# Digital_Port_K_State_LED_Inducator.net
KiCad netlist of a schematic drawn in Altium Designer
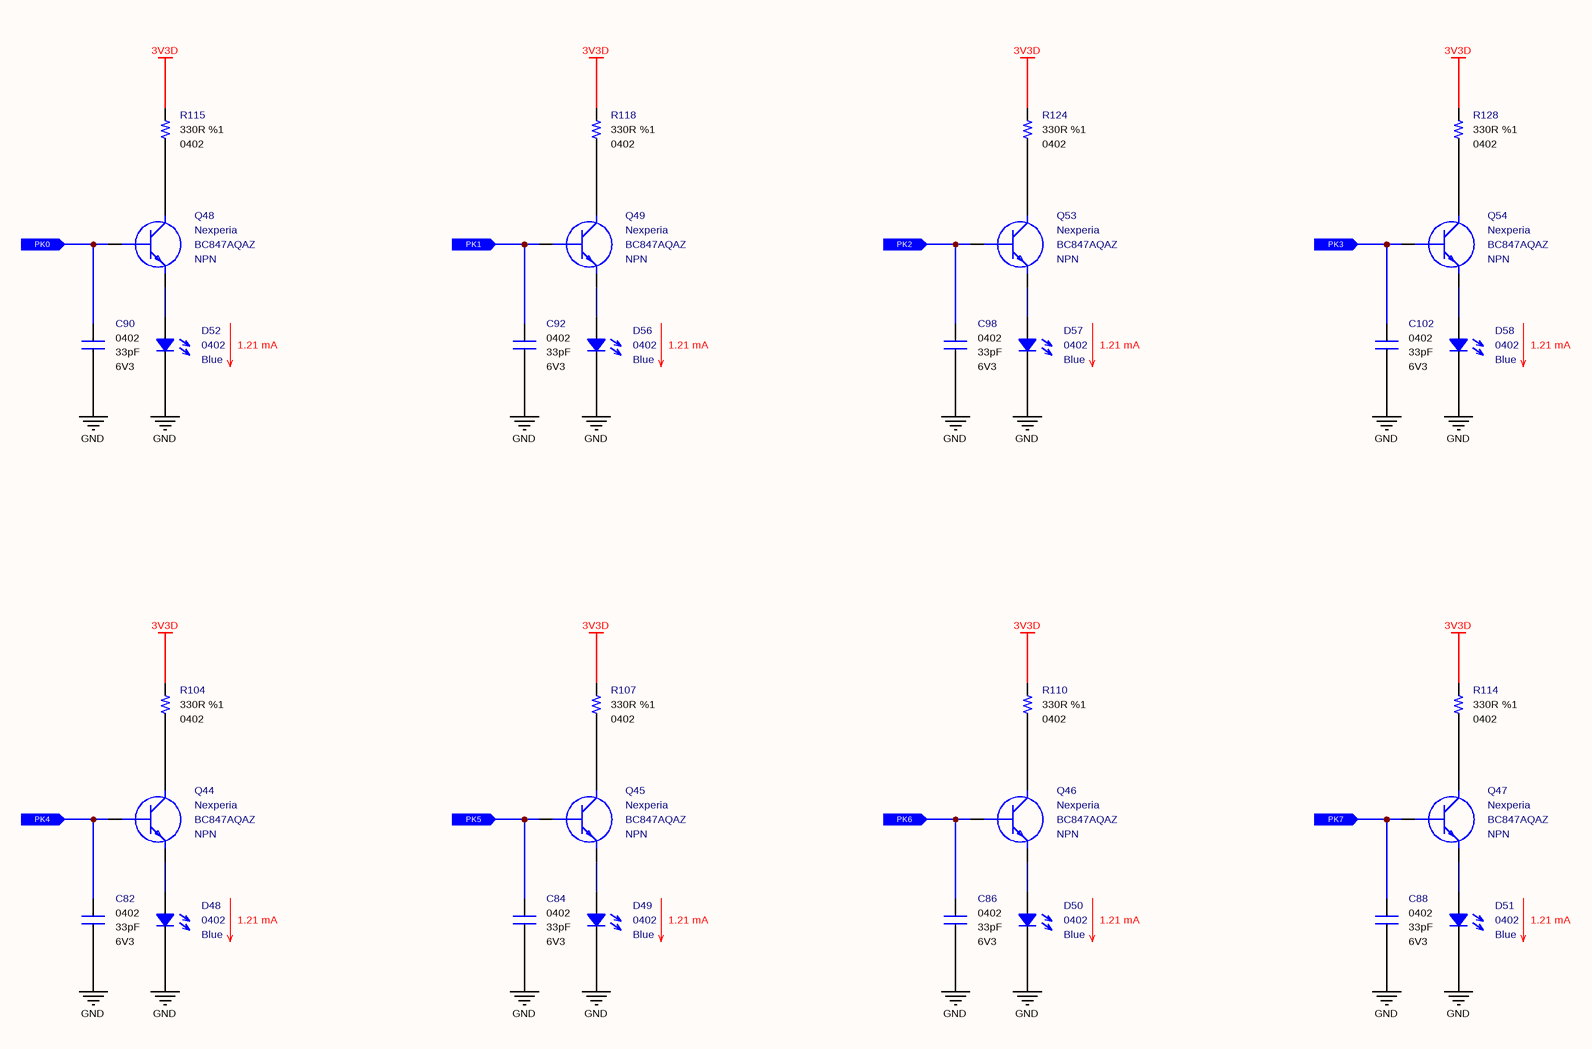
[diagram p0: Digital Port K State LED Inducator.SchDoc]

(export (version "E")
  (design (tool "Eeschema 10.0.6"))
  (components
    (comp (ref "C82")
      (value "33pF")
      (footprint "CAPACITOR_0402")
      (description "Capacitor - 33pF [0402] (Ceramic)")
      (fields
        (field (name "CASE") "0402")
        (field (name "TOLERANCE") "10%")
        (field (name "VOLTAGE") "6V3")
        (field (name "MANUFACTURER PART NUMBER") "C0402C330J9RACAUTO")
      )
      (libsource (lib "Ovoo_Library") (part "Capacitor - 33pF [0402-6V3]"))
    )
    (comp (ref "C84")
      (value "33pF")
      (footprint "CAPACITOR_0402")
      (description "Capacitor - 33pF [0402] (Ceramic)")
      (fields
        (field (name "CASE") "0402")
        (field (name "TOLERANCE") "10%")
        (field (name "VOLTAGE") "6V3")
        (field (name "MANUFACTURER PART NUMBER") "C0402C330J9RACAUTO")
      )
      (libsource (lib "Ovoo_Library") (part "Capacitor - 33pF [0402-6V3]"))
    )
    (comp (ref "C86")
      (value "33pF")
      (footprint "CAPACITOR_0402")
      (description "Capacitor - 33pF [0402] (Ceramic)")
      (fields
        (field (name "CASE") "0402")
        (field (name "TOLERANCE") "10%")
        (field (name "VOLTAGE") "6V3")
        (field (name "MANUFACTURER PART NUMBER") "C0402C330J9RACAUTO")
      )
      (libsource (lib "Ovoo_Library") (part "Capacitor - 33pF [0402-6V3]"))
    )
    (comp (ref "C88")
      (value "33pF")
      (footprint "CAPACITOR_0402")
      (description "Capacitor - 33pF [0402] (Ceramic)")
      (fields
        (field (name "CASE") "0402")
        (field (name "TOLERANCE") "10%")
        (field (name "VOLTAGE") "6V3")
        (field (name "MANUFACTURER PART NUMBER") "C0402C330J9RACAUTO")
      )
      (libsource (lib "Ovoo_Library") (part "Capacitor - 33pF [0402-6V3]"))
    )
    (comp (ref "C90")
      (value "33pF")
      (footprint "CAPACITOR_0402")
      (description "Capacitor - 33pF [0402] (Ceramic)")
      (fields
        (field (name "CASE") "0402")
        (field (name "TOLERANCE") "10%")
        (field (name "VOLTAGE") "6V3")
        (field (name "MANUFACTURER PART NUMBER") "C0402C330J9RACAUTO")
      )
      (libsource (lib "Ovoo_Library") (part "Capacitor - 33pF [0402-6V3]"))
    )
    (comp (ref "C92")
      (value "33pF")
      (footprint "CAPACITOR_0402")
      (description "Capacitor - 33pF [0402] (Ceramic)")
      (fields
        (field (name "CASE") "0402")
        (field (name "TOLERANCE") "10%")
        (field (name "VOLTAGE") "6V3")
        (field (name "MANUFACTURER PART NUMBER") "C0402C330J9RACAUTO")
      )
      (libsource (lib "Ovoo_Library") (part "Capacitor - 33pF [0402-6V3]"))
    )
    (comp (ref "C98")
      (value "33pF")
      (footprint "CAPACITOR_0402")
      (description "Capacitor - 33pF [0402] (Ceramic)")
      (fields
        (field (name "CASE") "0402")
        (field (name "TOLERANCE") "10%")
        (field (name "VOLTAGE") "6V3")
        (field (name "MANUFACTURER PART NUMBER") "C0402C330J9RACAUTO")
      )
      (libsource (lib "Ovoo_Library") (part "Capacitor - 33pF [0402-6V3]"))
    )
    (comp (ref "C102")
      (value "33pF")
      (footprint "CAPACITOR_0402")
      (description "Capacitor - 33pF [0402] (Ceramic)")
      (fields
        (field (name "CASE") "0402")
        (field (name "TOLERANCE") "10%")
        (field (name "VOLTAGE") "6V3")
        (field (name "MANUFACTURER PART NUMBER") "C0402C330J9RACAUTO")
      )
      (libsource (lib "Ovoo_Library") (part "Capacitor - 33pF [0402-6V3]"))
    )
    (comp (ref "D48")
      (value "SMD LED (Blue)")
      (footprint "LED_0402")
      (description "Standard LEDs - SMD PICOLEDTM;BLUE LED; 25M @ 5MA")
      (fields
        (field (name "MANUFACTURER_PART_NUMBER") "SMLP13BC8TT86")
        (field (name "MOUSER_PART_NUMBER") "755-SMLP13BC8TT86")
        (field (name "CASE") "0402")
        (field (name "COLOR") "Blue")
      )
      (libsource (lib "Ovoo_Library") (part "Diode - LED (0402-Blue)"))
    )
    (comp (ref "D49")
      (value "SMD LED (Blue)")
      (footprint "LED_0402")
      (description "Standard LEDs - SMD PICOLEDTM;BLUE LED; 25M @ 5MA")
      (fields
        (field (name "MANUFACTURER_PART_NUMBER") "SMLP13BC8TT86")
        (field (name "MOUSER_PART_NUMBER") "755-SMLP13BC8TT86")
        (field (name "CASE") "0402")
        (field (name "COLOR") "Blue")
      )
      (libsource (lib "Ovoo_Library") (part "Diode - LED (0402-Blue)"))
    )
    (comp (ref "D50")
      (value "SMD LED (Blue)")
      (footprint "LED_0402")
      (description "Standard LEDs - SMD PICOLEDTM;BLUE LED; 25M @ 5MA")
      (fields
        (field (name "MANUFACTURER_PART_NUMBER") "SMLP13BC8TT86")
        (field (name "MOUSER_PART_NUMBER") "755-SMLP13BC8TT86")
        (field (name "CASE") "0402")
        (field (name "COLOR") "Blue")
      )
      (libsource (lib "Ovoo_Library") (part "Diode - LED (0402-Blue)"))
    )
    (comp (ref "D51")
      (value "SMD LED (Blue)")
      (footprint "LED_0402")
      (description "Standard LEDs - SMD PICOLEDTM;BLUE LED; 25M @ 5MA")
      (fields
        (field (name "MANUFACTURER_PART_NUMBER") "SMLP13BC8TT86")
        (field (name "MOUSER_PART_NUMBER") "755-SMLP13BC8TT86")
        (field (name "CASE") "0402")
        (field (name "COLOR") "Blue")
      )
      (libsource (lib "Ovoo_Library") (part "Diode - LED (0402-Blue)"))
    )
    (comp (ref "D52")
      (value "SMD LED (Blue)")
      (footprint "LED_0402")
      (description "Standard LEDs - SMD PICOLEDTM;BLUE LED; 25M @ 5MA")
      (fields
        (field (name "MANUFACTURER_PART_NUMBER") "SMLP13BC8TT86")
        (field (name "MOUSER_PART_NUMBER") "755-SMLP13BC8TT86")
        (field (name "CASE") "0402")
        (field (name "COLOR") "Blue")
      )
      (libsource (lib "Ovoo_Library") (part "Diode - LED (0402-Blue)"))
    )
    (comp (ref "D56")
      (value "SMD LED (Blue)")
      (footprint "LED_0402")
      (description "Standard LEDs - SMD PICOLEDTM;BLUE LED; 25M @ 5MA")
      (fields
        (field (name "MANUFACTURER_PART_NUMBER") "SMLP13BC8TT86")
        (field (name "MOUSER_PART_NUMBER") "755-SMLP13BC8TT86")
        (field (name "CASE") "0402")
        (field (name "COLOR") "Blue")
      )
      (libsource (lib "Ovoo_Library") (part "Diode - LED (0402-Blue)"))
    )
    (comp (ref "D57")
      (value "SMD LED (Blue)")
      (footprint "LED_0402")
      (description "Standard LEDs - SMD PICOLEDTM;BLUE LED; 25M @ 5MA")
      (fields
        (field (name "MANUFACTURER_PART_NUMBER") "SMLP13BC8TT86")
        (field (name "MOUSER_PART_NUMBER") "755-SMLP13BC8TT86")
        (field (name "CASE") "0402")
        (field (name "COLOR") "Blue")
      )
      (libsource (lib "Ovoo_Library") (part "Diode - LED (0402-Blue)"))
    )
    (comp (ref "D58")
      (value "SMD LED (Blue)")
      (footprint "LED_0402")
      (description "Standard LEDs - SMD PICOLEDTM;BLUE LED; 25M @ 5MA")
      (fields
        (field (name "MANUFACTURER_PART_NUMBER") "SMLP13BC8TT86")
        (field (name "MOUSER_PART_NUMBER") "755-SMLP13BC8TT86")
        (field (name "CASE") "0402")
        (field (name "COLOR") "Blue")
      )
      (libsource (lib "Ovoo_Library") (part "Diode - LED (0402-Blue)"))
    )
    (comp (ref "Q44")
      (value "Bipolar NPN Transistors")
      (footprint "SOT1215")
      (description "Bipolar Transistors - BJT BC847AQA/DFN1010D-3/REEL 7\" Q2")
      (fields
        (field (name "MOUSER_PART_NUMBER") "771-BC847AQAZ")
        (field (name "MANUFACTURER_NAME") "Nexperia")
        (field (name "MANUFACTURER_PART_NUMBER") "BC847AQAZ")
        (field (name "POLARITY") "NPN")
      )
      (libsource (lib "Ovoo_Library") (part "Transistor - BC847"))
    )
    (comp (ref "Q45")
      (value "Bipolar NPN Transistors")
      (footprint "SOT1215")
      (description "Bipolar Transistors - BJT BC847AQA/DFN1010D-3/REEL 7\" Q2")
      (fields
        (field (name "MOUSER_PART_NUMBER") "771-BC847AQAZ")
        (field (name "MANUFACTURER_NAME") "Nexperia")
        (field (name "MANUFACTURER_PART_NUMBER") "BC847AQAZ")
        (field (name "POLARITY") "NPN")
      )
      (libsource (lib "Ovoo_Library") (part "Transistor - BC847"))
    )
    (comp (ref "Q46")
      (value "Bipolar NPN Transistors")
      (footprint "SOT1215")
      (description "Bipolar Transistors - BJT BC847AQA/DFN1010D-3/REEL 7\" Q2")
      (fields
        (field (name "MOUSER_PART_NUMBER") "771-BC847AQAZ")
        (field (name "MANUFACTURER_NAME") "Nexperia")
        (field (name "MANUFACTURER_PART_NUMBER") "BC847AQAZ")
        (field (name "POLARITY") "NPN")
      )
      (libsource (lib "Ovoo_Library") (part "Transistor - BC847"))
    )
    (comp (ref "Q47")
      (value "Bipolar NPN Transistors")
      (footprint "SOT1215")
      (description "Bipolar Transistors - BJT BC847AQA/DFN1010D-3/REEL 7\" Q2")
      (fields
        (field (name "MOUSER_PART_NUMBER") "771-BC847AQAZ")
        (field (name "MANUFACTURER_NAME") "Nexperia")
        (field (name "MANUFACTURER_PART_NUMBER") "BC847AQAZ")
        (field (name "POLARITY") "NPN")
      )
      (libsource (lib "Ovoo_Library") (part "Transistor - BC847"))
    )
    (comp (ref "Q48")
      (value "Bipolar NPN Transistors")
      (footprint "SOT1215")
      (description "Bipolar Transistors - BJT BC847AQA/DFN1010D-3/REEL 7\" Q2")
      (fields
        (field (name "MOUSER_PART_NUMBER") "771-BC847AQAZ")
        (field (name "MANUFACTURER_NAME") "Nexperia")
        (field (name "MANUFACTURER_PART_NUMBER") "BC847AQAZ")
        (field (name "POLARITY") "NPN")
      )
      (libsource (lib "Ovoo_Library") (part "Transistor - BC847"))
    )
    (comp (ref "Q49")
      (value "Bipolar NPN Transistors")
      (footprint "SOT1215")
      (description "Bipolar Transistors - BJT BC847AQA/DFN1010D-3/REEL 7\" Q2")
      (fields
        (field (name "MOUSER_PART_NUMBER") "771-BC847AQAZ")
        (field (name "MANUFACTURER_NAME") "Nexperia")
        (field (name "MANUFACTURER_PART_NUMBER") "BC847AQAZ")
        (field (name "POLARITY") "NPN")
      )
      (libsource (lib "Ovoo_Library") (part "Transistor - BC847"))
    )
    (comp (ref "Q53")
      (value "Bipolar NPN Transistors")
      (footprint "SOT1215")
      (description "Bipolar Transistors - BJT BC847AQA/DFN1010D-3/REEL 7\" Q2")
      (fields
        (field (name "MOUSER_PART_NUMBER") "771-BC847AQAZ")
        (field (name "MANUFACTURER_NAME") "Nexperia")
        (field (name "MANUFACTURER_PART_NUMBER") "BC847AQAZ")
        (field (name "POLARITY") "NPN")
      )
      (libsource (lib "Ovoo_Library") (part "Transistor - BC847"))
    )
    (comp (ref "Q54")
      (value "Bipolar NPN Transistors")
      (footprint "SOT1215")
      (description "Bipolar Transistors - BJT BC847AQA/DFN1010D-3/REEL 7\" Q2")
      (fields
        (field (name "MOUSER_PART_NUMBER") "771-BC847AQAZ")
        (field (name "MANUFACTURER_NAME") "Nexperia")
        (field (name "MANUFACTURER_PART_NUMBER") "BC847AQAZ")
        (field (name "POLARITY") "NPN")
      )
      (libsource (lib "Ovoo_Library") (part "Transistor - BC847"))
    )
    (comp (ref "R104")
      (value "330R")
      (footprint "RESISTOR_0402")
      (description "Thick Film Resistors - SMD 1/16 W 330 Ohm 1%")
      (fields
        (field (name "TOLERANCE") "%1")
        (field (name "CASE") "0402")
        (field (name "MANUFACTURER PART NUMBER") "CRCW0402330RFKED")
        (field (name "MOUSER PART NUMBER") "71-CRCW0402-330-E3")
      )
      (libsource (lib "Ovoo_Library") (part "Resistor - 330R"))
    )
    (comp (ref "R107")
      (value "330R")
      (footprint "RESISTOR_0402")
      (description "Thick Film Resistors - SMD 1/16 W 330 Ohm 1%")
      (fields
        (field (name "TOLERANCE") "%1")
        (field (name "CASE") "0402")
        (field (name "MANUFACTURER PART NUMBER") "CRCW0402330RFKED")
        (field (name "MOUSER PART NUMBER") "71-CRCW0402-330-E3")
      )
      (libsource (lib "Ovoo_Library") (part "Resistor - 330R"))
    )
    (comp (ref "R110")
      (value "330R")
      (footprint "RESISTOR_0402")
      (description "Thick Film Resistors - SMD 1/16 W 330 Ohm 1%")
      (fields
        (field (name "TOLERANCE") "%1")
        (field (name "CASE") "0402")
        (field (name "MANUFACTURER PART NUMBER") "CRCW0402330RFKED")
        (field (name "MOUSER PART NUMBER") "71-CRCW0402-330-E3")
      )
      (libsource (lib "Ovoo_Library") (part "Resistor - 330R"))
    )
    (comp (ref "R114")
      (value "330R")
      (footprint "RESISTOR_0402")
      (description "Thick Film Resistors - SMD 1/16 W 330 Ohm 1%")
      (fields
        (field (name "TOLERANCE") "%1")
        (field (name "CASE") "0402")
        (field (name "MANUFACTURER PART NUMBER") "CRCW0402330RFKED")
        (field (name "MOUSER PART NUMBER") "71-CRCW0402-330-E3")
      )
      (libsource (lib "Ovoo_Library") (part "Resistor - 330R"))
    )
    (comp (ref "R115")
      (value "330R")
      (footprint "RESISTOR_0402")
      (description "Thick Film Resistors - SMD 1/16 W 330 Ohm 1%")
      (fields
        (field (name "TOLERANCE") "%1")
        (field (name "CASE") "0402")
        (field (name "MANUFACTURER PART NUMBER") "CRCW0402330RFKED")
        (field (name "MOUSER PART NUMBER") "71-CRCW0402-330-E3")
      )
      (libsource (lib "Ovoo_Library") (part "Resistor - 330R"))
    )
    (comp (ref "R118")
      (value "330R")
      (footprint "RESISTOR_0402")
      (description "Thick Film Resistors - SMD 1/16 W 330 Ohm 1%")
      (fields
        (field (name "TOLERANCE") "%1")
        (field (name "CASE") "0402")
        (field (name "MANUFACTURER PART NUMBER") "CRCW0402330RFKED")
        (field (name "MOUSER PART NUMBER") "71-CRCW0402-330-E3")
      )
      (libsource (lib "Ovoo_Library") (part "Resistor - 330R"))
    )
    (comp (ref "R124")
      (value "330R")
      (footprint "RESISTOR_0402")
      (description "Thick Film Resistors - SMD 1/16 W 330 Ohm 1%")
      (fields
        (field (name "TOLERANCE") "%1")
        (field (name "CASE") "0402")
        (field (name "MANUFACTURER PART NUMBER") "CRCW0402330RFKED")
        (field (name "MOUSER PART NUMBER") "71-CRCW0402-330-E3")
      )
      (libsource (lib "Ovoo_Library") (part "Resistor - 330R"))
    )
    (comp (ref "R128")
      (value "330R")
      (footprint "RESISTOR_0402")
      (description "Thick Film Resistors - SMD 1/16 W 330 Ohm 1%")
      (fields
        (field (name "TOLERANCE") "%1")
        (field (name "CASE") "0402")
        (field (name "MANUFACTURER PART NUMBER") "CRCW0402330RFKED")
        (field (name "MOUSER PART NUMBER") "71-CRCW0402-330-E3")
      )
      (libsource (lib "Ovoo_Library") (part "Resistor - 330R"))
    )
  )
  (nets
    (net (code "1") (name "/PK0") (class "Default")
      (node (ref "C90") (pin "1") (pinfunction "1_1") (pintype "passive"))
      (node (ref "Q48") (pin "1") (pinfunction "B_1") (pintype "passive"))
    )
    (net (code "2") (name "/PK1") (class "Default")
      (node (ref "C92") (pin "1") (pinfunction "1_1") (pintype "passive"))
      (node (ref "Q49") (pin "1") (pinfunction "B_1") (pintype "passive"))
    )
    (net (code "3") (name "/PK2") (class "Default")
      (node (ref "C98") (pin "1") (pinfunction "1_1") (pintype "passive"))
      (node (ref "Q53") (pin "1") (pinfunction "B_1") (pintype "passive"))
    )
    (net (code "4") (name "/PK3") (class "Default")
      (node (ref "C102") (pin "1") (pinfunction "1_1") (pintype "passive"))
      (node (ref "Q54") (pin "1") (pinfunction "B_1") (pintype "passive"))
    )
    (net (code "5") (name "/PK4") (class "Default")
      (node (ref "C82") (pin "1") (pinfunction "1_1") (pintype "passive"))
      (node (ref "Q44") (pin "1") (pinfunction "B_1") (pintype "passive"))
    )
    (net (code "6") (name "/PK5") (class "Default")
      (node (ref "C84") (pin "1") (pinfunction "1_1") (pintype "passive"))
      (node (ref "Q45") (pin "1") (pinfunction "B_1") (pintype "passive"))
    )
    (net (code "7") (name "/PK6") (class "Default")
      (node (ref "C86") (pin "1") (pinfunction "1_1") (pintype "passive"))
      (node (ref "Q46") (pin "1") (pinfunction "B_1") (pintype "passive"))
    )
    (net (code "8") (name "/PK7") (class "Default")
      (node (ref "C88") (pin "1") (pinfunction "1_1") (pintype "passive"))
      (node (ref "Q47") (pin "1") (pinfunction "B_1") (pintype "passive"))
    )
    (net (code "9") (name "3V3D") (class "Default")
      (node (ref "R104") (pin "2") (pinfunction "2_2") (pintype "passive"))
      (node (ref "R107") (pin "2") (pinfunction "2_2") (pintype "passive"))
      (node (ref "R110") (pin "2") (pinfunction "2_2") (pintype "passive"))
      (node (ref "R114") (pin "2") (pinfunction "2_2") (pintype "passive"))
      (node (ref "R115") (pin "2") (pinfunction "2_2") (pintype "passive"))
      (node (ref "R118") (pin "2") (pinfunction "2_2") (pintype "passive"))
      (node (ref "R124") (pin "2") (pinfunction "2_2") (pintype "passive"))
      (node (ref "R128") (pin "2") (pinfunction "2_2") (pintype "passive"))
    )
    (net (code "10") (name "GND") (class "Default")
      (node (ref "C102") (pin "2") (pinfunction "2_2") (pintype "passive"))
      (node (ref "C82") (pin "2") (pinfunction "2_2") (pintype "passive"))
      (node (ref "C84") (pin "2") (pinfunction "2_2") (pintype "passive"))
      (node (ref "C86") (pin "2") (pinfunction "2_2") (pintype "passive"))
      (node (ref "C88") (pin "2") (pinfunction "2_2") (pintype "passive"))
      (node (ref "C90") (pin "2") (pinfunction "2_2") (pintype "passive"))
      (node (ref "C92") (pin "2") (pinfunction "2_2") (pintype "passive"))
      (node (ref "C98") (pin "2") (pinfunction "2_2") (pintype "passive"))
      (node (ref "D48") (pin "1") (pinfunction "1_1") (pintype "passive"))
      (node (ref "D49") (pin "1") (pinfunction "1_1") (pintype "passive"))
      (node (ref "D50") (pin "1") (pinfunction "1_1") (pintype "passive"))
      (node (ref "D51") (pin "1") (pinfunction "1_1") (pintype "passive"))
      (node (ref "D52") (pin "1") (pinfunction "1_1") (pintype "passive"))
      (node (ref "D56") (pin "1") (pinfunction "1_1") (pintype "passive"))
      (node (ref "D57") (pin "1") (pinfunction "1_1") (pintype "passive"))
      (node (ref "D58") (pin "1") (pinfunction "1_1") (pintype "passive"))
    )
    (net (code "11") (name "Net-(Q44-C)") (class "Default")
      (node (ref "Q44") (pin "3") (pinfunction "C_3") (pintype "passive"))
      (node (ref "R104") (pin "1") (pinfunction "1_1") (pintype "passive"))
    )
    (net (code "12") (name "Net-(Q44-E)") (class "Default")
      (node (ref "D48") (pin "2") (pinfunction "2_2") (pintype "passive"))
      (node (ref "Q44") (pin "2") (pinfunction "E_2") (pintype "passive"))
    )
    (net (code "13") (name "Net-(Q45-C)") (class "Default")
      (node (ref "Q45") (pin "3") (pinfunction "C_3") (pintype "passive"))
      (node (ref "R107") (pin "1") (pinfunction "1_1") (pintype "passive"))
    )
    (net (code "14") (name "Net-(Q45-E)") (class "Default")
      (node (ref "D49") (pin "2") (pinfunction "2_2") (pintype "passive"))
      (node (ref "Q45") (pin "2") (pinfunction "E_2") (pintype "passive"))
    )
    (net (code "15") (name "Net-(Q46-C)") (class "Default")
      (node (ref "Q46") (pin "3") (pinfunction "C_3") (pintype "passive"))
      (node (ref "R110") (pin "1") (pinfunction "1_1") (pintype "passive"))
    )
    (net (code "16") (name "Net-(Q46-E)") (class "Default")
      (node (ref "D50") (pin "2") (pinfunction "2_2") (pintype "passive"))
      (node (ref "Q46") (pin "2") (pinfunction "E_2") (pintype "passive"))
    )
    (net (code "17") (name "Net-(Q47-C)") (class "Default")
      (node (ref "Q47") (pin "3") (pinfunction "C_3") (pintype "passive"))
      (node (ref "R114") (pin "1") (pinfunction "1_1") (pintype "passive"))
    )
    (net (code "18") (name "Net-(Q47-E)") (class "Default")
      (node (ref "D51") (pin "2") (pinfunction "2_2") (pintype "passive"))
      (node (ref "Q47") (pin "2") (pinfunction "E_2") (pintype "passive"))
    )
    (net (code "19") (name "Net-(Q48-C)") (class "Default")
      (node (ref "Q48") (pin "3") (pinfunction "C_3") (pintype "passive"))
      (node (ref "R115") (pin "1") (pinfunction "1_1") (pintype "passive"))
    )
    (net (code "20") (name "Net-(Q48-E)") (class "Default")
      (node (ref "D52") (pin "2") (pinfunction "2_2") (pintype "passive"))
      (node (ref "Q48") (pin "2") (pinfunction "E_2") (pintype "passive"))
    )
    (net (code "21") (name "Net-(Q49-C)") (class "Default")
      (node (ref "Q49") (pin "3") (pinfunction "C_3") (pintype "passive"))
      (node (ref "R118") (pin "1") (pinfunction "1_1") (pintype "passive"))
    )
    (net (code "22") (name "Net-(Q49-E)") (class "Default")
      (node (ref "D56") (pin "2") (pinfunction "2_2") (pintype "passive"))
      (node (ref "Q49") (pin "2") (pinfunction "E_2") (pintype "passive"))
    )
    (net (code "23") (name "Net-(Q53-C)") (class "Default")
      (node (ref "Q53") (pin "3") (pinfunction "C_3") (pintype "passive"))
      (node (ref "R124") (pin "1") (pinfunction "1_1") (pintype "passive"))
    )
    (net (code "24") (name "Net-(Q53-E)") (class "Default")
      (node (ref "D57") (pin "2") (pinfunction "2_2") (pintype "passive"))
      (node (ref "Q53") (pin "2") (pinfunction "E_2") (pintype "passive"))
    )
    (net (code "25") (name "Net-(Q54-C)") (class "Default")
      (node (ref "Q54") (pin "3") (pinfunction "C_3") (pintype "passive"))
      (node (ref "R128") (pin "1") (pinfunction "1_1") (pintype "passive"))
    )
    (net (code "26") (name "Net-(Q54-E)") (class "Default")
      (node (ref "D58") (pin "2") (pinfunction "2_2") (pintype "passive"))
      (node (ref "Q54") (pin "2") (pinfunction "E_2") (pintype "passive"))
    )
  )
)
